# Schematic.net
KiCad netlist of a schematic drawn in Altium Designer
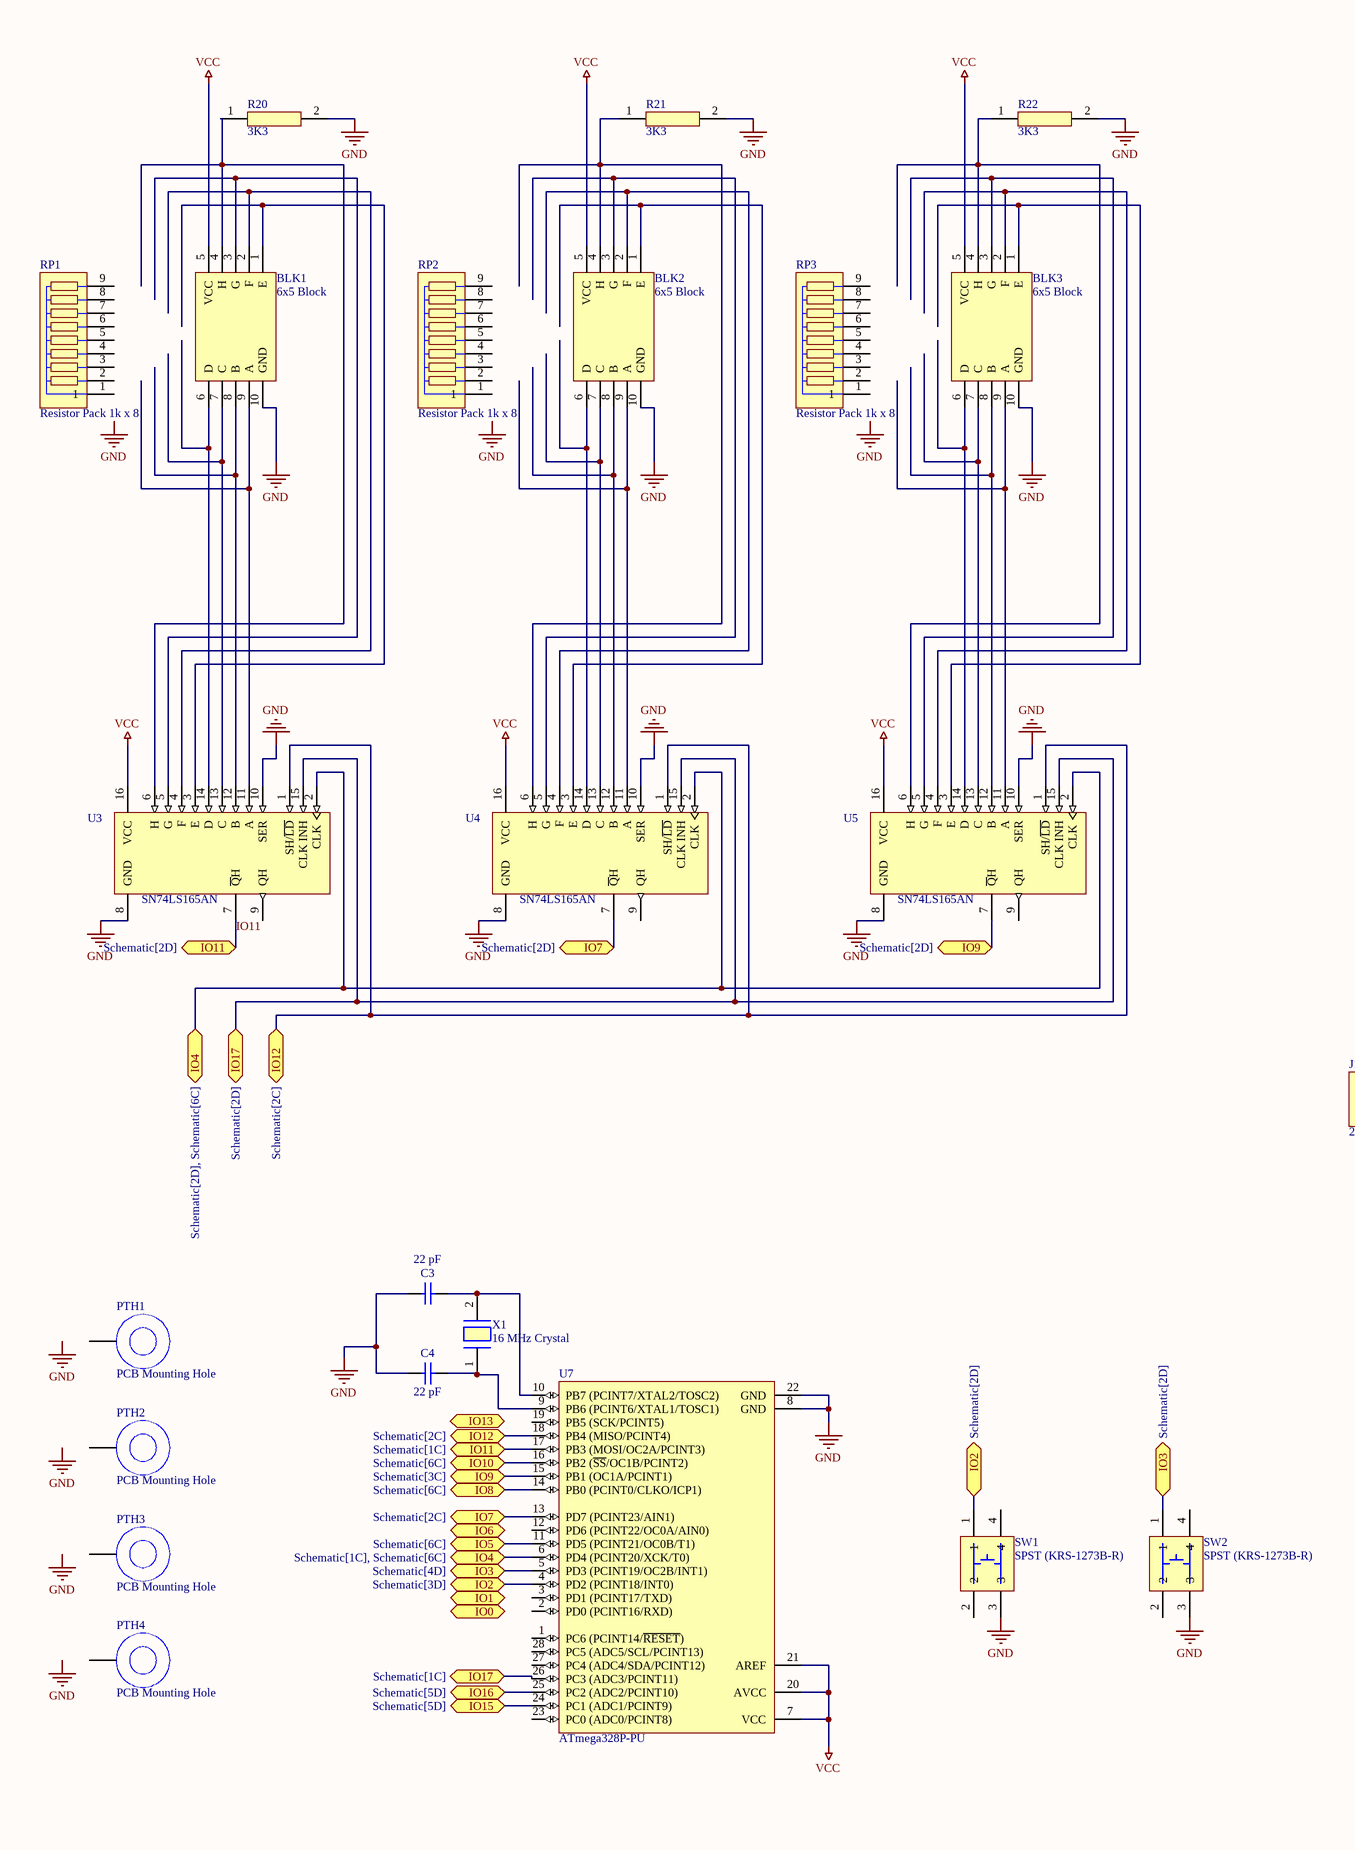
[diagram p0: Schematic.SchDoc, left]
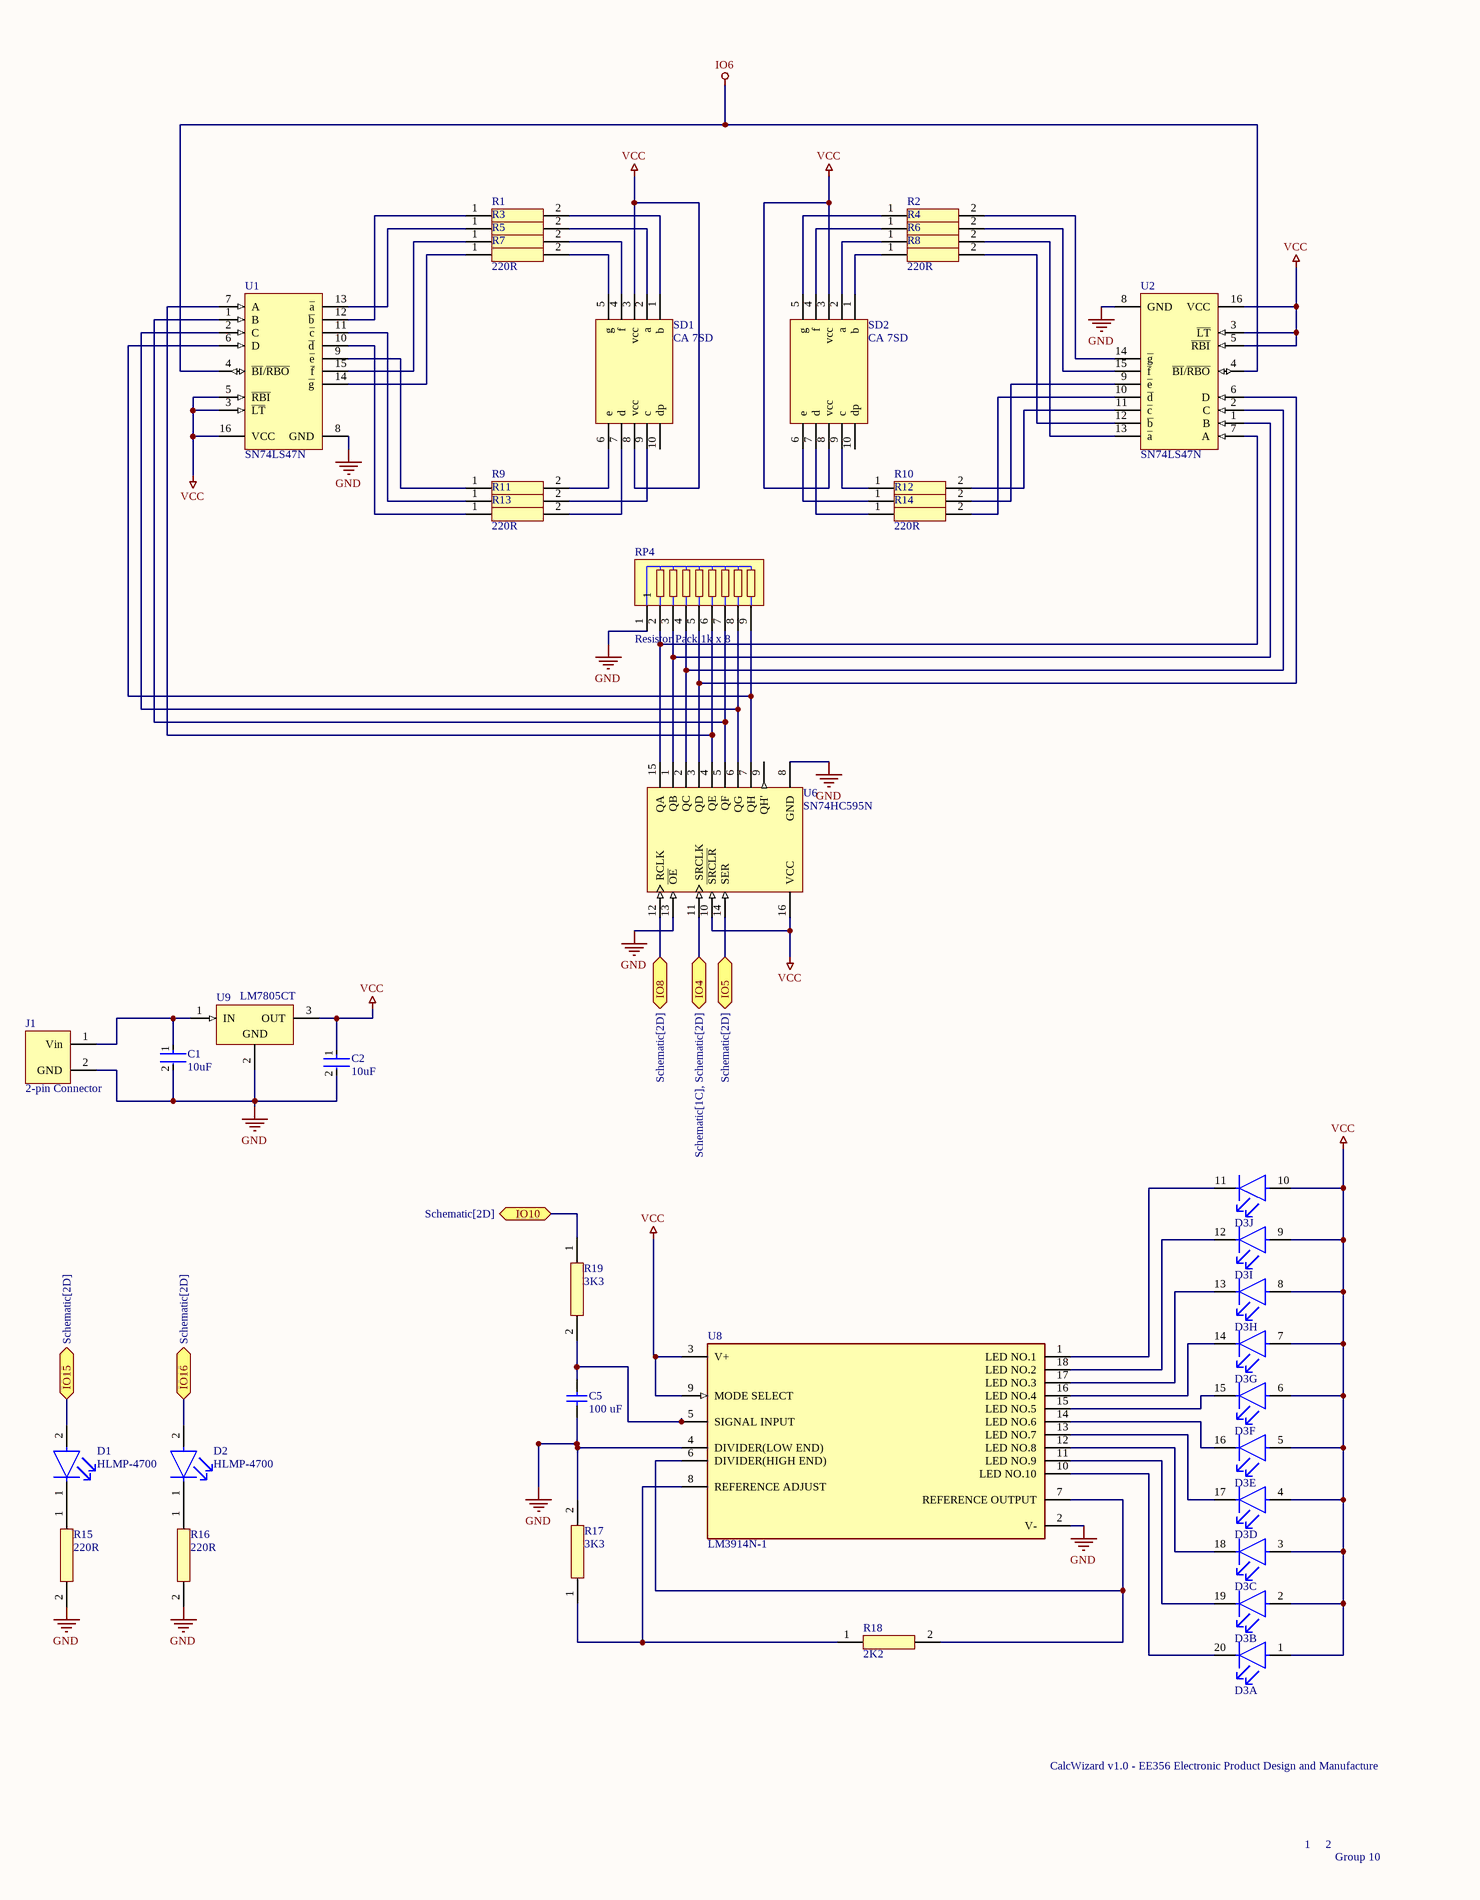
[diagram p1: Schematic.SchDoc, right]

(export (version "E")
  (design (tool "Eeschema 10.0.6"))
  (components
    (comp (ref "BLK1")
      (value "6x5 Block")
      (footprint "Block_6x5")
      (libsource (lib "Schlib1") (part "Block_6x5"))
    )
    (comp (ref "BLK2")
      (value "6x5 Block")
      (footprint "Block_6x5")
      (libsource (lib "Schlib1") (part "Block_6x5"))
    )
    (comp (ref "BLK3")
      (value "6x5 Block")
      (footprint "Block_6x5")
      (libsource (lib "Schlib1") (part "Block_6x5"))
    )
    (comp (ref "C1")
      (value "10uF")
      (footprint "FP-RCE3DB-MFG")
      (description "Cap Ceramic 10uF 25V X7R ±10% Radial 2.5mm +125°C Automotive Bulk (RCER71E106K3A2H03B)")
      (fields (field (name "TOLERANCE") "10%"))
      (libsource (lib "Altium Content Vault") (part "b4654b650e69147ec39a6b967a45e02"))
    )
    (comp (ref "C2")
      (value "10uF")
      (footprint "FP-RCE3DB-MFG")
      (description "Cap Ceramic 10uF 25V X7R ±10% Radial 2.5mm +125°C Automotive Bulk (RCER71E106K3A2H03B)")
      (fields (field (name "TOLERANCE") "10%"))
      (libsource (lib "Altium Content Vault") (part "b4654b650e69147ec39a6b967a45e02"))
    )
    (comp (ref "C3")
      (value "22 pF")
      (footprint "KEMT-C315-THT-2")
      (description "Capacitor, Ceramic, 22 pF, +/-10 %, 100 V, -55 to 125 degC, 2-Pin THD, RoHS, Bulk")
      (libsource (lib "Altium Content Vault") (part "CAP-NP-2"))
    )
    (comp (ref "C4")
      (value "22 pF")
      (footprint "KEMT-C315-THT-2")
      (description "Capacitor, Ceramic, 22 pF, +/-10 %, 100 V, -55 to 125 degC, 2-Pin THD, RoHS, Bulk")
      (libsource (lib "Altium Content Vault") (part "CAP-NP-2"))
    )
    (comp (ref "C5")
      (value "100 uF")
      (footprint "KEMT-C315-THT-2")
      (description "Capacitor, Ceramic, 100 uF, +/-10 %, 100 V, -55 to 125 degC, 2-Pin THD, RoHS, Bulk")
      (libsource (lib "Altium Content Vault") (part "CAP-NP-2"))
    )
    (comp (ref "D1")
      (value "HLMP-4700")
      (footprint "FP-HLMP-4700-MFG")
      (description "LED RED DIFFUSED T-1 3/4 T/H")
      (fields
        (field (name "OCTOPART") "https://octopart.com/hlmp-4700-broadcom-71130526")
        (field (name "MANUFACTURER") "Broadcom")
      )
      (libsource (lib "Altium Content Vault") (part "8706943c75ba83719d021d2fdc84c58"))
    )
    (comp (ref "D2")
      (value "HLMP-4700")
      (footprint "FP-HLMP-4700-MFG")
      (description "LED RED DIFFUSED T-1 3/4 T/H")
      (fields
        (field (name "OCTOPART") "https://octopart.com/hlmp-4700-broadcom-71130526")
        (field (name "MANUFACTURER") "Broadcom")
      )
      (libsource (lib "Altium Content Vault") (part "8706943c75ba83719d021d2fdc84c58"))
    )
    (comp (ref "D3")
      (value "SSA-LXB10HW-GF/LP")
      (footprint "FP-SSA-LXB10HW-GF-LP-MFG")
      (description "LED ARRAY 10X25MM 10SEG RED DIFF")
      (fields
        (field (name "OCTOPART") "https://octopart.com/ssa-lxb10hw-gf%2Flp-lumex-548235")
        (field (name "MANUFACTURER") "lumex")
      )
      (libsource (lib "Altium Content Vault") (part "0ad3f8813297581e4dba16f0763b6c7"))
    )
    (comp (ref "J1")
      (value "2-pin Connector")
      (footprint "2-pin Connector")
      (description "Female, 2C, Straight, .100\"CC; 3.20mm Tail, No Mt. 100u\" Tin; PBT, Phos Bronze, 105 C")
      (fields
        (field (name "MANUFACTURER") "Sullins")
        (field (name "MANUFACTURER PART NUMBER") "PPTC021LFBN-RC")
      )
      (libsource (lib "Schlib1") (part "PPTC021LFBN-RC"))
    )
    (comp (ref "PTH1")
      (value "PCB Mounting Hole")
      (footprint "PTH 2mm")
      (libsource (lib "Schlib1") (part "PTH"))
    )
    (comp (ref "PTH2")
      (value "PCB Mounting Hole")
      (footprint "PTH 2mm")
      (libsource (lib "Schlib1") (part "PTH"))
    )
    (comp (ref "PTH3")
      (value "PCB Mounting Hole")
      (footprint "PTH 2mm")
      (libsource (lib "Schlib1") (part "PTH"))
    )
    (comp (ref "PTH4")
      (value "PCB Mounting Hole")
      (footprint "PTH 2mm")
      (libsource (lib "Schlib1") (part "PTH"))
    )
    (comp (ref "R1")
      (value "220R")
      (footprint "CFR_400mil")
      (description "General Type Carbon Film Resistor 220Ohm 1/4W 5% Axial Bulk")
      (fields
        (field (name "MANUFACTURER") "Yageo")
        (field (name "MANUFACTURER PART NUMBER") "CFR-25JB-52-220R")
      )
      (libsource (lib "Schlib1") (part "CFR-25JB-52-220R"))
    )
    (comp (ref "R2")
      (value "220R")
      (footprint "CFR_400mil")
      (description "General Type Carbon Film Resistor 220Ohm 1/4W 5% Axial Bulk")
      (fields
        (field (name "MANUFACTURER") "Yageo")
        (field (name "MANUFACTURER PART NUMBER") "CFR-25JB-52-220R")
      )
      (libsource (lib "Schlib1") (part "CFR-25JB-52-220R"))
    )
    (comp (ref "R3")
      (value "220R")
      (footprint "CFR_400mil")
      (description "General Type Carbon Film Resistor 220Ohm 1/4W 5% Axial Bulk")
      (fields
        (field (name "MANUFACTURER") "Yageo")
        (field (name "MANUFACTURER PART NUMBER") "CFR-25JB-52-220R")
      )
      (libsource (lib "Schlib1") (part "CFR-25JB-52-220R"))
    )
    (comp (ref "R4")
      (value "220R")
      (footprint "CFR_400mil")
      (description "General Type Carbon Film Resistor 220Ohm 1/4W 5% Axial Bulk")
      (fields
        (field (name "MANUFACTURER") "Yageo")
        (field (name "MANUFACTURER PART NUMBER") "CFR-25JB-52-220R")
      )
      (libsource (lib "Schlib1") (part "CFR-25JB-52-220R"))
    )
    (comp (ref "R5")
      (value "220R")
      (footprint "CFR_400mil")
      (description "General Type Carbon Film Resistor 220Ohm 1/4W 5% Axial Bulk")
      (fields
        (field (name "MANUFACTURER") "Yageo")
        (field (name "MANUFACTURER PART NUMBER") "CFR-25JB-52-220R")
      )
      (libsource (lib "Schlib1") (part "CFR-25JB-52-220R"))
    )
    (comp (ref "R6")
      (value "220R")
      (footprint "CFR_400mil")
      (description "General Type Carbon Film Resistor 220Ohm 1/4W 5% Axial Bulk")
      (fields
        (field (name "MANUFACTURER") "Yageo")
        (field (name "MANUFACTURER PART NUMBER") "CFR-25JB-52-220R")
      )
      (libsource (lib "Schlib1") (part "CFR-25JB-52-220R"))
    )
    (comp (ref "R7")
      (value "220R")
      (footprint "CFR_400mil")
      (description "General Type Carbon Film Resistor 220Ohm 1/4W 5% Axial Bulk")
      (fields
        (field (name "MANUFACTURER") "Yageo")
        (field (name "MANUFACTURER PART NUMBER") "CFR-25JB-52-220R")
      )
      (libsource (lib "Schlib1") (part "CFR-25JB-52-220R"))
    )
    (comp (ref "R8")
      (value "220R")
      (footprint "CFR_400mil")
      (description "General Type Carbon Film Resistor 220Ohm 1/4W 5% Axial Bulk")
      (fields
        (field (name "MANUFACTURER") "Yageo")
        (field (name "MANUFACTURER PART NUMBER") "CFR-25JB-52-220R")
      )
      (libsource (lib "Schlib1") (part "CFR-25JB-52-220R"))
    )
    (comp (ref "R9")
      (value "220R")
      (footprint "CFR_400mil")
      (description "General Type Carbon Film Resistor 220Ohm 1/4W 5% Axial Bulk")
      (fields
        (field (name "MANUFACTURER") "Yageo")
        (field (name "MANUFACTURER PART NUMBER") "CFR-25JB-52-220R")
      )
      (libsource (lib "Schlib1") (part "CFR-25JB-52-220R"))
    )
    (comp (ref "R10")
      (value "220R")
      (footprint "CFR_400mil")
      (description "General Type Carbon Film Resistor 220Ohm 1/4W 5% Axial Bulk")
      (fields
        (field (name "MANUFACTURER") "Yageo")
        (field (name "MANUFACTURER PART NUMBER") "CFR-25JB-52-220R")
      )
      (libsource (lib "Schlib1") (part "CFR-25JB-52-220R"))
    )
    (comp (ref "R11")
      (value "220R")
      (footprint "CFR_400mil")
      (description "General Type Carbon Film Resistor 220Ohm 1/4W 5% Axial Bulk")
      (fields
        (field (name "MANUFACTURER") "Yageo")
        (field (name "MANUFACTURER PART NUMBER") "CFR-25JB-52-220R")
      )
      (libsource (lib "Schlib1") (part "CFR-25JB-52-220R"))
    )
    (comp (ref "R12")
      (value "220R")
      (footprint "CFR_400mil")
      (description "General Type Carbon Film Resistor 220Ohm 1/4W 5% Axial Bulk")
      (fields
        (field (name "MANUFACTURER") "Yageo")
        (field (name "MANUFACTURER PART NUMBER") "CFR-25JB-52-220R")
      )
      (libsource (lib "Schlib1") (part "CFR-25JB-52-220R"))
    )
    (comp (ref "R13")
      (value "220R")
      (footprint "CFR_400mil")
      (description "General Type Carbon Film Resistor 220Ohm 1/4W 5% Axial Bulk")
      (fields
        (field (name "MANUFACTURER") "Yageo")
        (field (name "MANUFACTURER PART NUMBER") "CFR-25JB-52-220R")
      )
      (libsource (lib "Schlib1") (part "CFR-25JB-52-220R"))
    )
    (comp (ref "R14")
      (value "220R")
      (footprint "CFR_400mil")
      (description "General Type Carbon Film Resistor 220Ohm 1/4W 5% Axial Bulk")
      (fields
        (field (name "MANUFACTURER") "Yageo")
        (field (name "MANUFACTURER PART NUMBER") "CFR-25JB-52-220R")
      )
      (libsource (lib "Schlib1") (part "CFR-25JB-52-220R"))
    )
    (comp (ref "R15")
      (value "220R")
      (footprint "CFR_400mil")
      (description "General Type Carbon Film Resistor 220Ohm 1/4W 5% Axial Bulk")
      (fields
        (field (name "MANUFACTURER") "Yageo")
        (field (name "MANUFACTURER PART NUMBER") "CFR-25JB-52-220R")
      )
      (libsource (lib "") (part "CFR-25JB-52-220R_1"))
    )
    (comp (ref "R16")
      (value "220R")
      (footprint "CFR_400mil")
      (description "General Type Carbon Film Resistor 220Ohm 1/4W 5% Axial Bulk")
      (fields
        (field (name "MANUFACTURER") "Yageo")
        (field (name "MANUFACTURER PART NUMBER") "CFR-25JB-52-220R")
      )
      (libsource (lib "") (part "CFR-25JB-52-220R_1"))
    )
    (comp (ref "R17")
      (value "3K3")
      (footprint "CFR_400mil")
      (description "General Type Carbon Film Resistor 3.3kOhm 1/4W 5% Axial Bulk")
      (fields
        (field (name "MANUFACTURER") "Yageo")
        (field (name "MANUFACTURER PART NUMBER") "CFR-25JB-52-220R")
      )
      (libsource (lib "Schlib1") (part "CFR-25JB-52-3K3"))
    )
    (comp (ref "R18")
      (value "2K2")
      (footprint "CFR_400mil")
      (description "General Type Carbon Film Resistor 2.2kOhm 1/4W 5% Axial Bulk")
      (fields
        (field (name "MANUFACTURER") "Yageo")
        (field (name "MANUFACTURER PART NUMBER") "CFR-25JB-52-220R")
      )
      (libsource (lib "Schlib1") (part "CFR-25JB-52-2K2"))
    )
    (comp (ref "R19")
      (value "3K3")
      (footprint "CFR_400mil")
      (description "General Type Carbon Film Resistor 3.3kOhm 1/4W 5% Axial Bulk")
      (fields
        (field (name "MANUFACTURER") "Yageo")
        (field (name "MANUFACTURER PART NUMBER") "CFR-25JB-52-220R")
      )
      (libsource (lib "") (part "CFR-25JB-52-3K3_2"))
    )
    (comp (ref "R20")
      (value "3K3")
      (footprint "CFR_400mil")
      (description "General Type Carbon Film Resistor 3.3kOhm 1/4W 5% Axial Bulk")
      (fields
        (field (name "MANUFACTURER") "Yageo")
        (field (name "MANUFACTURER PART NUMBER") "CFR-25JB-52-220R")
      )
      (libsource (lib "") (part "CFR-25JB-52-3K3_1"))
    )
    (comp (ref "R21")
      (value "3K3")
      (footprint "CFR_400mil")
      (description "General Type Carbon Film Resistor 3.3kOhm 1/4W 5% Axial Bulk")
      (fields
        (field (name "MANUFACTURER") "Yageo")
        (field (name "MANUFACTURER PART NUMBER") "CFR-25JB-52-220R")
      )
      (libsource (lib "") (part "CFR-25JB-52-3K3_1"))
    )
    (comp (ref "R22")
      (value "3K3")
      (footprint "CFR_400mil")
      (description "General Type Carbon Film Resistor 3.3kOhm 1/4W 5% Axial Bulk")
      (fields
        (field (name "MANUFACTURER") "Yageo")
        (field (name "MANUFACTURER PART NUMBER") "CFR-25JB-52-220R")
      )
      (libsource (lib "") (part "CFR-25JB-52-3K3_1"))
    )
    (comp (ref "RP1")
      (value "Resistor Pack 1k x 8")
      (footprint "Resistor Pack 1k x 8")
      (description "Res Thick Film NET 1K Ohm 2% 1.13W ±100ppm/°C BUS Molded 9-Pin SIP Pin Thru-Hole")
      (fields
        (field (name "MANUFACTURER") "Bourns")
        (field (name "MANUFACTURER PART NUMBER") "4309R-101-102LF")
      )
      (libsource (lib "") (part "4309R-101-102LF_1"))
    )
    (comp (ref "RP2")
      (value "Resistor Pack 1k x 8")
      (footprint "Resistor Pack 1k x 8")
      (description "Res Thick Film NET 1K Ohm 2% 1.13W ±100ppm/°C BUS Molded 9-Pin SIP Pin Thru-Hole")
      (fields
        (field (name "MANUFACTURER") "Bourns")
        (field (name "MANUFACTURER PART NUMBER") "4309R-101-102LF")
      )
      (libsource (lib "") (part "4309R-101-102LF_1"))
    )
    (comp (ref "RP3")
      (value "Resistor Pack 1k x 8")
      (footprint "Resistor Pack 1k x 8")
      (description "Res Thick Film NET 1K Ohm 2% 1.13W ±100ppm/°C BUS Molded 9-Pin SIP Pin Thru-Hole")
      (fields
        (field (name "MANUFACTURER") "Bourns")
        (field (name "MANUFACTURER PART NUMBER") "4309R-101-102LF")
      )
      (libsource (lib "") (part "4309R-101-102LF_1"))
    )
    (comp (ref "RP4")
      (value "Resistor Pack 1k x 8")
      (footprint "Resistor Pack 1k x 8")
      (description "Res Thick Film NET 1K Ohm 2% 1.13W ±100ppm/°C BUS Molded 9-Pin SIP Pin Thru-Hole")
      (fields
        (field (name "MANUFACTURER") "Bourns")
        (field (name "MANUFACTURER PART NUMBER") "4309R-101-102LF")
      )
      (libsource (lib "Schlib1") (part "4309R-101-102LF"))
    )
    (comp (ref "SD1")
      (value "CA 7SD")
      (footprint "CA 7SD")
      (description "Single Digit Seven Segment Green 0.56\" Common Anode Through Hole LED Display")
      (fields (field (name "MANUFACTURER") "Lumex") (field (name "MANUFACTURER PART NUMBER") "LDS-A5642RI"))
      (libsource (lib "Schlib1") (part "LDS-A5642RI"))
    )
    (comp (ref "SD2")
      (value "CA 7SD")
      (footprint "CA 7SD")
      (description "Single Digit Seven Segment Green 0.56\" Common Anode Through Hole LED Display")
      (fields (field (name "MANUFACTURER") "Lumex") (field (name "MANUFACTURER PART NUMBER") "LDS-A5642RI"))
      (libsource (lib "Schlib1") (part "LDS-A5642RI"))
    )
    (comp (ref "SW1")
      (value "SPST (KRS-1273B-R)")
      (footprint "SPST KRS-1273B-R")
      (description "Switch Push Button Tactile Off Momentary (On) Single Pole Single Throw Cap: 155389 155409")
      (fields
        (field (name "MANUFACTURER") "Jameco Valuepro")
        (field (name "MANUFACTURER PART NUMBER") "KRS-1273B-R")
      )
      (libsource (lib "Schlib1") (part "KRS-1273B-R"))
    )
    (comp (ref "SW2")
      (value "SPST (KRS-1273B-R)")
      (footprint "SPST KRS-1273B-R")
      (description "Switch Push Button Tactile Off Momentary (On) Single Pole Single Throw Cap: 155389 155409")
      (fields
        (field (name "MANUFACTURER") "Jameco Valuepro")
        (field (name "MANUFACTURER PART NUMBER") "KRS-1273B-R")
      )
      (libsource (lib "Schlib1") (part "KRS-1273B-R"))
    )
    (comp (ref "U1")
      (value "SN74LS47N")
      (footprint "N0016A")
      (description "BCD-to-7-Segment Decoder / Driver, 4.75 to 5.25 V, 0 to 70 degC, 16-pin DIP (N16), Pb-Free (RoHS)")
      (fields (field (name "MANUFACTURER") "Texas Instruments"))
      (libsource (lib "") (part "TI-SNX4XX247-16_1"))
    )
    (comp (ref "U2")
      (value "SN74LS47N")
      (footprint "N0016A")
      (description "BCD-to-7-Segment Decoder / Driver, 4.75 to 5.25 V, 0 to 70 degC, 16-pin DIP (N16), Pb-Free (RoHS)")
      (fields (field (name "MANUFACTURER") "Texas Instruments"))
      (libsource (lib "Altium Content Vault") (part "TI-SNX4XX247-16"))
    )
    (comp (ref "U3")
      (value "SN74LS165AN")
      (footprint "N0016A")
      (description "Serial-out shift registers, N0016A, TUBE")
      (fields
        (field (name "GENERIC PART NUMBER") "SN74LS165A")
        (field (name "MANUFACTURER") "Texas Instruments")
      )
      (libsource (lib "Altium Content Vault") (part "TI-SNX4XXX165X-16"))
    )
    (comp (ref "U4")
      (value "SN74LS165AN")
      (footprint "N0016A")
      (description "Serial-out shift registers, N0016A, TUBE")
      (fields
        (field (name "GENERIC PART NUMBER") "SN74LS165A")
        (field (name "MANUFACTURER") "Texas Instruments")
      )
      (libsource (lib "Altium Content Vault") (part "TI-SNX4XXX165X-16"))
    )
    (comp (ref "U5")
      (value "SN74LS165AN")
      (footprint "N0016A")
      (description "Serial-out shift registers, N0016A, TUBE")
      (fields
        (field (name "GENERIC PART NUMBER") "SN74LS165A")
        (field (name "MANUFACTURER") "Texas Instruments")
      )
      (libsource (lib "Altium Content Vault") (part "TI-SNX4XXX165X-16"))
    )
    (comp (ref "U6")
      (value "SN74HC595N")
      (footprint "N0016A")
      (description "8-Bit Shift Registers With 3-State Output Registers, N0016A, TUBE")
      (fields
        (field (name "GENERIC PART NUMBER") "SN74HC595")
        (field (name "MANUFACTURER") "Texas Instruments")
      )
      (libsource (lib "Altium Content Vault") (part "TI-SN74XHCT595X_SN74LV595A-16"))
    )
    (comp (ref "U7")
      (value "ATmega328P-PU")
      (footprint "28P3")
      (libsource (lib "Altium Content Vault") (part "MC-8B-ATM48-IL28"))
    )
    (comp (ref "U8")
      (value "LM3914N-1")
      (footprint "FP-NFK0018A-MFG")
      (description "IC DRVR DOT/BAR DISPLAY 18DIP")
      (libsource (lib "Altium Content Vault") (part "8d9105b9cf50def005be23956edfdd2"))
    )
    (comp (ref "U9")
      (value "LM7805CT")
      (footprint "FAIR-TO-220-3")
      (description "Positive Voltage Regulator, 5 V, 1 A, -40 to 125 degC, 3-Pin TO-220, RoHS, Tube")
      (fields (field (name "MANUFACTURER") "FairchildSemiconductor"))
      (libsource (lib "Altium Content Vault") (part "FAIR-LM7805CT-TO220-3"))
    )
    (comp (ref "X1")
      (value "16 MHz Crystal")
      (footprint "Crystal Osc TH")
      (description "Crystal 16MHz ±50ppm (Tol) ±50ppm (Stability) 20pF FUND 30Ohm 2-Pin DIP HC-49/S Thru-Hole Bulk")
      (fields (field (name "MANUFACTURER") "TXC") (field (name "MANUFACTURER PART NUMBER") "9B-16.000MBBK-B"))
      (libsource (lib "Schlib1") (part "9B-16.000MBBK-B"))
    )
  )
  (nets
    (net (code "3") (name "/IO2") (class "Default")
      (node (ref "SW1") (pin "1") (pinfunction "1_1") (pintype "passive"))
      (node (ref "U7") (pin "4") (pinfunction "PD2_(PCINT18/INT0)_4") (pintype "bidirectional"))
    )
    (net (code "4") (name "/IO3") (class "Default")
      (node (ref "SW2") (pin "1") (pinfunction "1_1") (pintype "passive"))
      (node (ref "U7") (pin "5") (pinfunction "PD3_(PCINT19/OC2B/INT1)_5") (pintype "bidirectional"))
    )
    (net (code "5") (name "/IO4") (class "Default")
      (node (ref "U3") (pin "2") (pinfunction "CLK_2") (pintype "input"))
      (node (ref "U4") (pin "2") (pinfunction "CLK_2") (pintype "input"))
      (node (ref "U5") (pin "2") (pinfunction "CLK_2") (pintype "input"))
      (node (ref "U6") (pin "11") (pinfunction "SRCLK_11") (pintype "input"))
      (node (ref "U7") (pin "6") (pinfunction "PD4_(PCINT20/XCK/T0)_6") (pintype "bidirectional"))
    )
    (net (code "6") (name "/IO5") (class "Default")
      (node (ref "U6") (pin "14") (pinfunction "SER_14") (pintype "input"))
      (node (ref "U7") (pin "11") (pinfunction "PD5_(PCINT21/OC0B/T1)_11") (pintype "bidirectional"))
    )
    (net (code "7") (name "/IO7") (class "Default")
      (node (ref "U4") (pin "7") (pinfunction "~{Q}H_7") (pintype "passive"))
      (node (ref "U7") (pin "13") (pinfunction "PD7_(PCINT23/AIN1)_13") (pintype "bidirectional"))
    )
    (net (code "8") (name "/IO8") (class "Default")
      (node (ref "U6") (pin "12") (pinfunction "RCLK_12") (pintype "input"))
      (node (ref "U7") (pin "14") (pinfunction "PB0_(PCINT0/CLKO/ICP1)_14") (pintype "bidirectional"))
    )
    (net (code "9") (name "/IO9") (class "Default")
      (node (ref "U5") (pin "7") (pinfunction "~{Q}H_7") (pintype "passive"))
      (node (ref "U7") (pin "15") (pinfunction "PB1_(OC1A/PCINT1)_15") (pintype "bidirectional"))
    )
    (net (code "10") (name "/IO10") (class "Default")
      (node (ref "R19") (pin "1") (pinfunction "1_1") (pintype "passive"))
      (node (ref "U7") (pin "16") (pinfunction "PB2_(~{SS}/OC1B/PCINT2)_16") (pintype "bidirectional"))
    )
    (net (code "11") (name "/IO11") (class "Default")
      (node (ref "U3") (pin "7") (pinfunction "~{Q}H_7") (pintype "passive"))
      (node (ref "U7") (pin "17") (pinfunction "PB3_(MOSI/OC2A/PCINT3)_17") (pintype "bidirectional"))
    )
    (net (code "12") (name "/IO12") (class "Default")
      (node (ref "U3") (pin "1") (pinfunction "SH/~{LD}_1") (pintype "input"))
      (node (ref "U4") (pin "1") (pinfunction "SH/~{LD}_1") (pintype "input"))
      (node (ref "U5") (pin "1") (pinfunction "SH/~{LD}_1") (pintype "input"))
      (node (ref "U7") (pin "18") (pinfunction "PB4_(MISO/PCINT4)_18") (pintype "bidirectional"))
    )
    (net (code "14") (name "/IO15") (class "Default")
      (node (ref "D1") (pin "2") (pinfunction "A_2") (pintype "passive"))
      (node (ref "U7") (pin "24") (pinfunction "PC1_(ADC1/PCINT9)_24") (pintype "bidirectional"))
    )
    (net (code "15") (name "/IO16") (class "Default")
      (node (ref "D2") (pin "2") (pinfunction "A_2") (pintype "passive"))
      (node (ref "U7") (pin "25") (pinfunction "PC2_(ADC2/PCINT10)_25") (pintype "bidirectional"))
    )
    (net (code "16") (name "/IO17") (class "Default")
      (node (ref "U3") (pin "15") (pinfunction "CLK_INH_15") (pintype "input"))
      (node (ref "U4") (pin "15") (pinfunction "CLK_INH_15") (pintype "input"))
      (node (ref "U5") (pin "15") (pinfunction "CLK_INH_15") (pintype "input"))
      (node (ref "U7") (pin "26") (pinfunction "PC3_(ADC3/PCINT11)_26") (pintype "bidirectional"))
    )
    (net (code "17") (name "GND") (class "Default")
      (node (ref "BLK1") (pin "10") (pinfunction "GND_10") (pintype "passive"))
      (node (ref "BLK2") (pin "10") (pinfunction "GND_10") (pintype "passive"))
      (node (ref "BLK3") (pin "10") (pinfunction "GND_10") (pintype "passive"))
      (node (ref "C1") (pin "2") (pinfunction "2_2") (pintype "passive"))
      (node (ref "C2") (pin "2") (pinfunction "2_2") (pintype "passive"))
      (node (ref "C3") (pin "1") (pinfunction "1_1") (pintype "passive"))
      (node (ref "C4") (pin "1") (pinfunction "1_1") (pintype "passive"))
      (node (ref "C5") (pin "1") (pinfunction "1_1") (pintype "passive"))
      (node (ref "J1") (pin "2") (pinfunction "GND_2") (pintype "passive"))
      (node (ref "R15") (pin "2") (pinfunction "2_2") (pintype "passive"))
      (node (ref "R16") (pin "2") (pinfunction "2_2") (pintype "passive"))
      (node (ref "R17") (pin "2") (pinfunction "2_2") (pintype "passive"))
      (node (ref "R20") (pin "2") (pinfunction "2_2") (pintype "passive"))
      (node (ref "R21") (pin "2") (pinfunction "2_2") (pintype "passive"))
      (node (ref "R22") (pin "2") (pinfunction "2_2") (pintype "passive"))
      (node (ref "RP4") (pin "1") (pinfunction "1_1") (pintype "passive"))
      (node (ref "SW1") (pin "3") (pinfunction "3_3") (pintype "passive"))
      (node (ref "SW2") (pin "3") (pinfunction "3_3") (pintype "passive"))
      (node (ref "U1") (pin "8") (pinfunction "GND_8") (pintype "power_in"))
      (node (ref "U2") (pin "8") (pinfunction "GND_8") (pintype "power_in"))
      (node (ref "U3") (pin "10") (pinfunction "SER_10") (pintype "input"))
      (node (ref "U3") (pin "8") (pinfunction "GND_8") (pintype "power_in"))
      (node (ref "U4") (pin "10") (pinfunction "SER_10") (pintype "input"))
      (node (ref "U4") (pin "8") (pinfunction "GND_8") (pintype "power_in"))
      (node (ref "U5") (pin "10") (pinfunction "SER_10") (pintype "input"))
      (node (ref "U5") (pin "8") (pinfunction "GND_8") (pintype "power_in"))
      (node (ref "U6") (pin "13") (pinfunction "~{OE}_13") (pintype "input"))
      (node (ref "U6") (pin "8") (pinfunction "GND_8") (pintype "power_in"))
      (node (ref "U7") (pin "22") (pinfunction "GND_22") (pintype "power_in"))
      (node (ref "U7") (pin "8") (pinfunction "GND_8") (pintype "power_in"))
      (node (ref "U8") (pin "2") (pinfunction "V-_2") (pintype "power_in"))
      (node (ref "U8") (pin "4") (pinfunction "DIVIDER(LOW_END)_4") (pintype "passive"))
      (node (ref "U9") (pin "2") (pinfunction "GND_2") (pintype "power_in"))
    )
    (net (code "18") (name "IO6") (class "Default")
      (node (ref "U1") (pin "4") (pinfunction "~{BI}/~{RBO}_4") (pintype "bidirectional"))
      (node (ref "U2") (pin "4") (pinfunction "~{BI}/~{RBO}_4") (pintype "bidirectional"))
    )
    (net (code "19") (name "Net-(BLK1-A)") (class "Default")
      (node (ref "BLK1") (pin "9") (pinfunction "A_9") (pintype "passive"))
      (node (ref "U3") (pin "11") (pinfunction "A_11") (pintype "input"))
    )
    (net (code "20") (name "Net-(BLK1-B)") (class "Default")
      (node (ref "BLK1") (pin "8") (pinfunction "B_8") (pintype "passive"))
      (node (ref "U3") (pin "12") (pinfunction "B_12") (pintype "input"))
    )
    (net (code "21") (name "Net-(BLK1-C)") (class "Default")
      (node (ref "BLK1") (pin "7") (pinfunction "C_7") (pintype "passive"))
      (node (ref "U3") (pin "13") (pinfunction "C_13") (pintype "input"))
    )
    (net (code "22") (name "Net-(BLK1-D)") (class "Default")
      (node (ref "BLK1") (pin "6") (pinfunction "D_6") (pintype "passive"))
      (node (ref "U3") (pin "14") (pinfunction "D_14") (pintype "input"))
    )
    (net (code "23") (name "Net-(BLK1-E)") (class "Default")
      (node (ref "BLK1") (pin "1") (pinfunction "E_1") (pintype "passive"))
      (node (ref "U3") (pin "3") (pinfunction "E_3") (pintype "input"))
    )
    (net (code "24") (name "Net-(BLK1-F)") (class "Default")
      (node (ref "BLK1") (pin "2") (pinfunction "F_2") (pintype "passive"))
      (node (ref "U3") (pin "4") (pinfunction "F_4") (pintype "input"))
    )
    (net (code "25") (name "Net-(BLK1-G)") (class "Default")
      (node (ref "BLK1") (pin "3") (pinfunction "G_3") (pintype "passive"))
      (node (ref "U3") (pin "5") (pinfunction "G_5") (pintype "input"))
    )
    (net (code "26") (name "Net-(BLK1-H)") (class "Default")
      (node (ref "BLK1") (pin "4") (pinfunction "H_4") (pintype "passive"))
      (node (ref "R20") (pin "1") (pinfunction "1_1") (pintype "passive"))
      (node (ref "U3") (pin "6") (pinfunction "H_6") (pintype "input"))
    )
    (net (code "27") (name "Net-(BLK2-A)") (class "Default")
      (node (ref "BLK2") (pin "9") (pinfunction "A_9") (pintype "passive"))
      (node (ref "U4") (pin "11") (pinfunction "A_11") (pintype "input"))
    )
    (net (code "28") (name "Net-(BLK2-B)") (class "Default")
      (node (ref "BLK2") (pin "8") (pinfunction "B_8") (pintype "passive"))
      (node (ref "U4") (pin "12") (pinfunction "B_12") (pintype "input"))
    )
    (net (code "29") (name "Net-(BLK2-C)") (class "Default")
      (node (ref "BLK2") (pin "7") (pinfunction "C_7") (pintype "passive"))
      (node (ref "U4") (pin "13") (pinfunction "C_13") (pintype "input"))
    )
    (net (code "30") (name "Net-(BLK2-D)") (class "Default")
      (node (ref "BLK2") (pin "6") (pinfunction "D_6") (pintype "passive"))
      (node (ref "U4") (pin "14") (pinfunction "D_14") (pintype "input"))
    )
    (net (code "31") (name "Net-(BLK2-E)") (class "Default")
      (node (ref "BLK2") (pin "1") (pinfunction "E_1") (pintype "passive"))
      (node (ref "U4") (pin "3") (pinfunction "E_3") (pintype "input"))
    )
    (net (code "32") (name "Net-(BLK2-F)") (class "Default")
      (node (ref "BLK2") (pin "2") (pinfunction "F_2") (pintype "passive"))
      (node (ref "U4") (pin "4") (pinfunction "F_4") (pintype "input"))
    )
    (net (code "33") (name "Net-(BLK2-G)") (class "Default")
      (node (ref "BLK2") (pin "3") (pinfunction "G_3") (pintype "passive"))
      (node (ref "U4") (pin "5") (pinfunction "G_5") (pintype "input"))
    )
    (net (code "34") (name "Net-(BLK2-H)") (class "Default")
      (node (ref "BLK2") (pin "4") (pinfunction "H_4") (pintype "passive"))
      (node (ref "R21") (pin "1") (pinfunction "1_1") (pintype "passive"))
      (node (ref "U4") (pin "6") (pinfunction "H_6") (pintype "input"))
    )
    (net (code "35") (name "Net-(BLK3-A)") (class "Default")
      (node (ref "BLK3") (pin "9") (pinfunction "A_9") (pintype "passive"))
      (node (ref "U5") (pin "11") (pinfunction "A_11") (pintype "input"))
    )
    (net (code "36") (name "Net-(BLK3-B)") (class "Default")
      (node (ref "BLK3") (pin "8") (pinfunction "B_8") (pintype "passive"))
      (node (ref "U5") (pin "12") (pinfunction "B_12") (pintype "input"))
    )
    (net (code "37") (name "Net-(BLK3-C)") (class "Default")
      (node (ref "BLK3") (pin "7") (pinfunction "C_7") (pintype "passive"))
      (node (ref "U5") (pin "13") (pinfunction "C_13") (pintype "input"))
    )
    (net (code "38") (name "Net-(BLK3-D)") (class "Default")
      (node (ref "BLK3") (pin "6") (pinfunction "D_6") (pintype "passive"))
      (node (ref "U5") (pin "14") (pinfunction "D_14") (pintype "input"))
    )
    (net (code "39") (name "Net-(BLK3-E)") (class "Default")
      (node (ref "BLK3") (pin "1") (pinfunction "E_1") (pintype "passive"))
      (node (ref "U5") (pin "3") (pinfunction "E_3") (pintype "input"))
    )
    (net (code "40") (name "Net-(BLK3-F)") (class "Default")
      (node (ref "BLK3") (pin "2") (pinfunction "F_2") (pintype "passive"))
      (node (ref "U5") (pin "4") (pinfunction "F_4") (pintype "input"))
    )
    (net (code "41") (name "Net-(BLK3-G)") (class "Default")
      (node (ref "BLK3") (pin "3") (pinfunction "G_3") (pintype "passive"))
      (node (ref "U5") (pin "5") (pinfunction "G_5") (pintype "input"))
    )
    (net (code "42") (name "Net-(BLK3-H)") (class "Default")
      (node (ref "BLK3") (pin "4") (pinfunction "H_4") (pintype "passive"))
      (node (ref "R22") (pin "1") (pinfunction "1_1") (pintype "passive"))
      (node (ref "U5") (pin "6") (pinfunction "H_6") (pintype "input"))
    )
    (net (code "43") (name "Net-(D1-C)") (class "Default")
      (node (ref "D1") (pin "1") (pinfunction "C_1") (pintype "passive"))
      (node (ref "R15") (pin "1") (pinfunction "1_1") (pintype "passive"))
    )
    (net (code "44") (name "Net-(D2-C)") (class "Default")
      (node (ref "D2") (pin "1") (pinfunction "C_1") (pintype "passive"))
      (node (ref "R16") (pin "1") (pinfunction "1_1") (pintype "passive"))
    )
    (net (code "45") (name "Net-(D3A-1_CATHODE)") (class "Default")
      (node (ref "D3") (pin "20") (pinfunction "1_CATHODE_20") (pintype "passive"))
      (node (ref "U8") (pin "10") (pinfunction "LED_NO.10_10") (pintype "passive"))
    )
    (net (code "46") (name "Net-(D3B-2_CATHODE)") (class "Default")
      (node (ref "D3") (pin "19") (pinfunction "2_CATHODE_19") (pintype "passive"))
      (node (ref "U8") (pin "11") (pinfunction "LED_NO.9_11") (pintype "passive"))
    )
    (net (code "47") (name "Net-(D3C-3_CATHODE)") (class "Default")
      (node (ref "D3") (pin "18") (pinfunction "3_CATHODE_18") (pintype "passive"))
      (node (ref "U8") (pin "12") (pinfunction "LED_NO.8_12") (pintype "passive"))
    )
    (net (code "48") (name "Net-(D3D-4_CATHODE)") (class "Default")
      (node (ref "D3") (pin "17") (pinfunction "4_CATHODE_17") (pintype "passive"))
      (node (ref "U8") (pin "13") (pinfunction "LED_NO.7_13") (pintype "passive"))
    )
    (net (code "49") (name "Net-(D3E-5_CATHODE)") (class "Default")
      (node (ref "D3") (pin "16") (pinfunction "5_CATHODE_16") (pintype "passive"))
      (node (ref "U8") (pin "14") (pinfunction "LED_NO.6_14") (pintype "passive"))
    )
    (net (code "50") (name "Net-(D3F-6_CATHODE)") (class "Default")
      (node (ref "D3") (pin "15") (pinfunction "6_CATHODE_15") (pintype "passive"))
      (node (ref "U8") (pin "15") (pinfunction "LED_NO.5_15") (pintype "passive"))
    )
    (net (code "51") (name "Net-(D3G-7_CATHODE)") (class "Default")
      (node (ref "D3") (pin "14") (pinfunction "7_CATHODE_14") (pintype "passive"))
      (node (ref "U8") (pin "16") (pinfunction "LED_NO.4_16") (pintype "passive"))
    )
    (net (code "52") (name "Net-(D3H-8_CATHODE)") (class "Default")
      (node (ref "D3") (pin "13") (pinfunction "8_CATHODE_13") (pintype "passive"))
      (node (ref "U8") (pin "17") (pinfunction "LED_NO.3_17") (pintype "passive"))
    )
    (net (code "53") (name "Net-(D3I-9_CATHODE)") (class "Default")
      (node (ref "D3") (pin "12") (pinfunction "9_CATHODE_12") (pintype "passive"))
      (node (ref "U8") (pin "18") (pinfunction "LED_NO.2_18") (pintype "passive"))
    )
    (net (code "54") (name "Net-(D3J-10_CATHODE)") (class "Default")
      (node (ref "D3") (pin "11") (pinfunction "10_CATHODE_11") (pintype "passive"))
      (node (ref "U8") (pin "1") (pinfunction "LED_NO.1_1") (pintype "passive"))
    )
    (net (code "55") (name "Net-(J1-Vin)") (class "Default")
      (node (ref "C1") (pin "1") (pinfunction "1_1") (pintype "passive"))
      (node (ref "J1") (pin "1") (pinfunction "Vin_1") (pintype "passive"))
      (node (ref "U9") (pin "1") (pinfunction "IN_1") (pintype "input"))
    )
    (net (code "56") (name "Net-(SD1-a)") (class "Default")
      (node (ref "R3") (pin "2") (pinfunction "2_2") (pintype "passive"))
      (node (ref "SD1") (pin "2") (pinfunction "a_2") (pintype "passive"))
    )
    (net (code "57") (name "Net-(SD1-b)") (class "Default")
      (node (ref "R1") (pin "2") (pinfunction "2_2") (pintype "passive"))
      (node (ref "SD1") (pin "1") (pinfunction "b_1") (pintype "passive"))
    )
    (net (code "58") (name "Net-(SD1-c)") (class "Default")
      (node (ref "R11") (pin "2") (pinfunction "2_2") (pintype "passive"))
      (node (ref "SD1") (pin "9") (pinfunction "c_9") (pintype "passive"))
    )
    (net (code "59") (name "Net-(SD1-d)") (class "Default")
      (node (ref "R13") (pin "2") (pinfunction "2_2") (pintype "passive"))
      (node (ref "SD1") (pin "7") (pinfunction "d_7") (pintype "passive"))
    )
    (net (code "60") (name "Net-(SD1-e)") (class "Default")
      (node (ref "R9") (pin "2") (pinfunction "2_2") (pintype "passive"))
      (node (ref "SD1") (pin "6") (pinfunction "e_6") (pintype "passive"))
    )
    (net (code "61") (name "Net-(SD1-f)") (class "Default")
      (node (ref "R5") (pin "2") (pinfunction "2_2") (pintype "passive"))
      (node (ref "SD1") (pin "4") (pinfunction "f_4") (pintype "passive"))
    )
    (net (code "62") (name "Net-(SD1-g)") (class "Default")
      (node (ref "R7") (pin "2") (pinfunction "2_2") (pintype "passive"))
      (node (ref "SD1") (pin "5") (pinfunction "g_5") (pintype "passive"))
    )
    (net (code "63") (name "Net-(SD2-a)") (class "Default")
      (node (ref "R6") (pin "1") (pinfunction "1_1") (pintype "passive"))
      (node (ref "SD2") (pin "2") (pinfunction "a_2") (pintype "passive"))
    )
    (net (code "64") (name "Net-(SD2-b)") (class "Default")
      (node (ref "R8") (pin "1") (pinfunction "1_1") (pintype "passive"))
      (node (ref "SD2") (pin "1") (pinfunction "b_1") (pintype "passive"))
    )
    (net (code "65") (name "Net-(SD2-c)") (class "Default")
      (node (ref "R10") (pin "1") (pinfunction "1_1") (pintype "passive"))
      (node (ref "SD2") (pin "9") (pinfunction "c_9") (pintype "passive"))
    )
    (net (code "66") (name "Net-(SD2-d)") (class "Default")
      (node (ref "R14") (pin "1") (pinfunction "1_1") (pintype "passive"))
      (node (ref "SD2") (pin "7") (pinfunction "d_7") (pintype "passive"))
    )
    (net (code "67") (name "Net-(SD2-e)") (class "Default")
      (node (ref "R12") (pin "1") (pinfunction "1_1") (pintype "passive"))
      (node (ref "SD2") (pin "6") (pinfunction "e_6") (pintype "passive"))
    )
    (net (code "68") (name "Net-(SD2-f)") (class "Default")
      (node (ref "R4") (pin "1") (pinfunction "1_1") (pintype "passive"))
      (node (ref "SD2") (pin "4") (pinfunction "f_4") (pintype "passive"))
    )
    (net (code "69") (name "Net-(SD2-g)") (class "Default")
      (node (ref "R2") (pin "1") (pinfunction "1_1") (pintype "passive"))
      (node (ref "SD2") (pin "5") (pinfunction "g_5") (pintype "passive"))
    )
    (net (code "70") (name "Net-(U1-A)") (class "Default")
      (node (ref "RP4") (pin "6") (pinfunction "6_6") (pintype "passive"))
      (node (ref "U1") (pin "7") (pinfunction "A_7") (pintype "input"))
      (node (ref "U6") (pin "4") (pinfunction "QE_4") (pintype "tri_state"))
    )
    (net (code "71") (name "Net-(U1-B)") (class "Default")
      (node (ref "RP4") (pin "7") (pinfunction "7_7") (pintype "passive"))
      (node (ref "U1") (pin "1") (pinfunction "B_1") (pintype "input"))
      (node (ref "U6") (pin "5") (pinfunction "QF_5") (pintype "tri_state"))
    )
    (net (code "72") (name "Net-(U1-C)") (class "Default")
      (node (ref "RP4") (pin "8") (pinfunction "8_8") (pintype "passive"))
      (node (ref "U1") (pin "2") (pinfunction "C_2") (pintype "input"))
      (node (ref "U6") (pin "6") (pinfunction "QG_6") (pintype "tri_state"))
    )
    (net (code "73") (name "Net-(U1-D)") (class "Default")
      (node (ref "RP4") (pin "9") (pinfunction "9_9") (pintype "passive"))
      (node (ref "U1") (pin "6") (pinfunction "D_6") (pintype "input"))
      (node (ref "U6") (pin "7") (pinfunction "QH_7") (pintype "tri_state"))
    )
    (net (code "74") (name "Net-(U1-~{a})") (class "Default")
      (node (ref "R3") (pin "1") (pinfunction "1_1") (pintype "passive"))
      (node (ref "U1") (pin "13") (pinfunction "~{a}_13") (pintype "open_collector"))
    )
    (net (code "75") (name "Net-(U1-~{b})") (class "Default")
      (node (ref "R1") (pin "1") (pinfunction "1_1") (pintype "passive"))
      (node (ref "U1") (pin "12") (pinfunction "~{b}_12") (pintype "open_collector"))
    )
    (net (code "76") (name "Net-(U1-~{c})") (class "Default")
      (node (ref "R11") (pin "1") (pinfunction "1_1") (pintype "passive"))
      (node (ref "U1") (pin "11") (pinfunction "~{c}_11") (pintype "open_collector"))
    )
    (net (code "77") (name "Net-(U1-~{d})") (class "Default")
      (node (ref "R13") (pin "1") (pinfunction "1_1") (pintype "passive"))
      (node (ref "U1") (pin "10") (pinfunction "~{d}_10") (pintype "open_collector"))
    )
    (net (code "78") (name "Net-(U1-~{e})") (class "Default")
      (node (ref "R9") (pin "1") (pinfunction "1_1") (pintype "passive"))
      (node (ref "U1") (pin "9") (pinfunction "~{e}_9") (pintype "open_collector"))
    )
    (net (code "79") (name "Net-(U1-~{f})") (class "Default")
      (node (ref "R5") (pin "1") (pinfunction "1_1") (pintype "passive"))
      (node (ref "U1") (pin "15") (pinfunction "~{f}_15") (pintype "open_collector"))
    )
    (net (code "80") (name "Net-(U1-~{g})") (class "Default")
      (node (ref "R7") (pin "1") (pinfunction "1_1") (pintype "passive"))
      (node (ref "U1") (pin "14") (pinfunction "~{g}_14") (pintype "open_collector"))
    )
    (net (code "81") (name "Net-(U2-A)") (class "Default")
      (node (ref "RP4") (pin "2") (pinfunction "2_2") (pintype "passive"))
      (node (ref "U2") (pin "7") (pinfunction "A_7") (pintype "input"))
      (node (ref "U6") (pin "15") (pinfunction "QA_15") (pintype "tri_state"))
    )
    (net (code "82") (name "Net-(U2-B)") (class "Default")
      (node (ref "RP4") (pin "3") (pinfunction "3_3") (pintype "passive"))
      (node (ref "U2") (pin "1") (pinfunction "B_1") (pintype "input"))
      (node (ref "U6") (pin "1") (pinfunction "QB_1") (pintype "tri_state"))
    )
    (net (code "83") (name "Net-(U2-C)") (class "Default")
      (node (ref "RP4") (pin "4") (pinfunction "4_4") (pintype "passive"))
      (node (ref "U2") (pin "2") (pinfunction "C_2") (pintype "input"))
      (node (ref "U6") (pin "2") (pinfunction "QC_2") (pintype "tri_state"))
    )
    (net (code "84") (name "Net-(U2-D)") (class "Default")
      (node (ref "RP4") (pin "5") (pinfunction "5_5") (pintype "passive"))
      (node (ref "U2") (pin "6") (pinfunction "D_6") (pintype "input"))
      (node (ref "U6") (pin "3") (pinfunction "QD_3") (pintype "tri_state"))
    )
    (net (code "85") (name "Net-(U2-~{a})") (class "Default")
      (node (ref "R6") (pin "2") (pinfunction "2_2") (pintype "passive"))
      (node (ref "U2") (pin "13") (pinfunction "~{a}_13") (pintype "open_collector"))
    )
    (net (code "86") (name "Net-(U2-~{b})") (class "Default")
      (node (ref "R8") (pin "2") (pinfunction "2_2") (pintype "passive"))
      (node (ref "U2") (pin "12") (pinfunction "~{b}_12") (pintype "open_collector"))
    )
    (net (code "87") (name "Net-(U2-~{c})") (class "Default")
      (node (ref "R10") (pin "2") (pinfunction "2_2") (pintype "passive"))
      (node (ref "U2") (pin "11") (pinfunction "~{c}_11") (pintype "open_collector"))
    )
    (net (code "88") (name "Net-(U2-~{d})") (class "Default")
      (node (ref "R14") (pin "2") (pinfunction "2_2") (pintype "passive"))
      (node (ref "U2") (pin "10") (pinfunction "~{d}_10") (pintype "open_collector"))
    )
    (net (code "89") (name "Net-(U2-~{e})") (class "Default")
      (node (ref "R12") (pin "2") (pinfunction "2_2") (pintype "passive"))
      (node (ref "U2") (pin "9") (pinfunction "~{e}_9") (pintype "open_collector"))
    )
    (net (code "90") (name "Net-(U2-~{f})") (class "Default")
      (node (ref "R4") (pin "2") (pinfunction "2_2") (pintype "passive"))
      (node (ref "U2") (pin "15") (pinfunction "~{f}_15") (pintype "open_collector"))
    )
    (net (code "91") (name "Net-(U2-~{g})") (class "Default")
      (node (ref "R2") (pin "2") (pinfunction "2_2") (pintype "passive"))
      (node (ref "U2") (pin "14") (pinfunction "~{g}_14") (pintype "open_collector"))
    )
    (net (code "92") (name "Net-(U7-PB6_(PCINT6{slash}XTAL1{slash}TOSC1))") (class "Default")
      (node (ref "C4") (pin "2") (pinfunction "2_2") (pintype "passive"))
      (node (ref "U7") (pin "9") (pinfunction "PB6_(PCINT6/XTAL1/TOSC1)_9") (pintype "bidirectional"))
      (node (ref "X1") (pin "1") (pinfunction "1_1") (pintype "passive"))
    )
    (net (code "93") (name "Net-(U7-PB7_(PCINT7{slash}XTAL2{slash}TOSC2))") (class "Default")
      (node (ref "C3") (pin "2") (pinfunction "2_2") (pintype "passive"))
      (node (ref "U7") (pin "10") (pinfunction "PB7_(PCINT7/XTAL2/TOSC2)_10") (pintype "bidirectional"))
      (node (ref "X1") (pin "2") (pinfunction "2_2") (pintype "passive"))
    )
    (net (code "94") (name "Net-(U8-DIVIDER(HIGH_END))") (class "Default")
      (node (ref "R18") (pin "2") (pinfunction "2_2") (pintype "passive"))
      (node (ref "U8") (pin "6") (pinfunction "DIVIDER(HIGH_END)_6") (pintype "passive"))
      (node (ref "U8") (pin "7") (pinfunction "REFERENCE_OUTPUT_7") (pintype "passive"))
    )
    (net (code "95") (name "Net-(U8-REFERENCE_ADJUST)") (class "Default")
      (node (ref "R17") (pin "1") (pinfunction "1_1") (pintype "passive"))
      (node (ref "R18") (pin "1") (pinfunction "1_1") (pintype "passive"))
      (node (ref "U8") (pin "8") (pinfunction "REFERENCE_ADJUST_8") (pintype "passive"))
    )
    (net (code "96") (name "Net-(U8-SIGNAL_INPUT)") (class "Default")
      (node (ref "C5") (pin "2") (pinfunction "2_2") (pintype "passive"))
      (node (ref "R19") (pin "2") (pinfunction "2_2") (pintype "passive"))
      (node (ref "U8") (pin "5") (pinfunction "SIGNAL_INPUT_5") (pintype "passive"))
    )
    (net (code "97") (name "VCC") (class "Default")
      (node (ref "BLK1") (pin "5") (pinfunction "VCC_5") (pintype "passive"))
      (node (ref "BLK2") (pin "5") (pinfunction "VCC_5") (pintype "passive"))
      (node (ref "BLK3") (pin "5") (pinfunction "VCC_5") (pintype "passive"))
      (node (ref "C2") (pin "1") (pinfunction "1_1") (pintype "passive"))
      (node (ref "D3") (pin "1") (pinfunction "1_ANODE_1") (pintype "passive"))
      (node (ref "D3") (pin "10") (pinfunction "10_ANODE_10") (pintype "passive"))
      (node (ref "D3") (pin "2") (pinfunction "2_ANODE_2") (pintype "passive"))
      (node (ref "D3") (pin "3") (pinfunction "3_ANODE_3") (pintype "passive"))
      (node (ref "D3") (pin "4") (pinfunction "4_ANODE_4") (pintype "passive"))
      (node (ref "D3") (pin "5") (pinfunction "5_ANODE_5") (pintype "passive"))
      (node (ref "D3") (pin "6") (pinfunction "6_ANODE_6") (pintype "passive"))
      (node (ref "D3") (pin "7") (pinfunction "7_ANODE_7") (pintype "passive"))
      (node (ref "D3") (pin "8") (pinfunction "8_ANODE_8") (pintype "passive"))
      (node (ref "D3") (pin "9") (pinfunction "9_ANODE_9") (pintype "passive"))
      (node (ref "SD1") (pin "3") (pinfunction "vcc_3") (pintype "passive"))
      (node (ref "SD1") (pin "8") (pinfunction "vcc_8") (pintype "passive"))
      (node (ref "SD2") (pin "3") (pinfunction "vcc_3") (pintype "passive"))
      (node (ref "SD2") (pin "8") (pinfunction "vcc_8") (pintype "passive"))
      (node (ref "U1") (pin "16") (pinfunction "VCC_16") (pintype "power_in"))
      (node (ref "U1") (pin "3") (pinfunction "~{LT}_3") (pintype "input"))
      (node (ref "U1") (pin "5") (pinfunction "~{RBI}_5") (pintype "input"))
      (node (ref "U2") (pin "16") (pinfunction "VCC_16") (pintype "power_in"))
      (node (ref "U2") (pin "3") (pinfunction "~{LT}_3") (pintype "input"))
      (node (ref "U2") (pin "5") (pinfunction "~{RBI}_5") (pintype "input"))
      (node (ref "U3") (pin "16") (pinfunction "VCC_16") (pintype "power_in"))
      (node (ref "U4") (pin "16") (pinfunction "VCC_16") (pintype "power_in"))
      (node (ref "U5") (pin "16") (pinfunction "VCC_16") (pintype "power_in"))
      (node (ref "U6") (pin "10") (pinfunction "~{SRCLR}_10") (pintype "input"))
      (node (ref "U6") (pin "16") (pinfunction "VCC_16") (pintype "power_in"))
      (node (ref "U7") (pin "20") (pinfunction "AVCC_20") (pintype "power_in"))
      (node (ref "U7") (pin "21") (pinfunction "AREF_21") (pintype "power_in"))
      (node (ref "U7") (pin "7") (pinfunction "VCC_7") (pintype "power_in"))
      (node (ref "U8") (pin "3") (pinfunction "V+_3") (pintype "power_in"))
      (node (ref "U8") (pin "9") (pinfunction "MODE_SELECT_9") (pintype "input"))
      (node (ref "U9") (pin "3") (pinfunction "OUT_3") (pintype "passive"))
    )
    (net (code "98") (name "unconnected-(PTH1-Pad1)") (class "Default")
      (node (ref "PTH1") (pin "1") (pinfunction "1_1") (pintype "passive"))
    )
    (net (code "99") (name "unconnected-(PTH2-Pad1)") (class "Default")
      (node (ref "PTH2") (pin "1") (pinfunction "1_1") (pintype "passive"))
    )
    (net (code "100") (name "unconnected-(PTH3-Pad1)") (class "Default")
      (node (ref "PTH3") (pin "1") (pinfunction "1_1") (pintype "passive"))
    )
    (net (code "101") (name "unconnected-(PTH4-Pad1)") (class "Default")
      (node (ref "PTH4") (pin "1") (pinfunction "1_1") (pintype "passive"))
    )
    (net (code "102") (name "unconnected-(RP1-Pad1)") (class "Default")
      (node (ref "RP1") (pin "1") (pinfunction "1_1") (pintype "passive"))
    )
    (net (code "103") (name "unconnected-(RP1-Pad2)") (class "Default")
      (node (ref "RP1") (pin "2") (pinfunction "2_2") (pintype "passive"))
    )
    (net (code "104") (name "unconnected-(RP1-Pad3)") (class "Default")
      (node (ref "RP1") (pin "3") (pinfunction "3_3") (pintype "passive"))
    )
    (net (code "105") (name "unconnected-(RP1-Pad4)") (class "Default")
      (node (ref "RP1") (pin "4") (pinfunction "4_4") (pintype "passive"))
    )
    (net (code "106") (name "unconnected-(RP1-Pad5)") (class "Default")
      (node (ref "RP1") (pin "5") (pinfunction "5_5") (pintype "passive"))
    )
    (net (code "107") (name "unconnected-(RP1-Pad6)") (class "Default")
      (node (ref "RP1") (pin "6") (pinfunction "6_6") (pintype "passive"))
    )
    (net (code "108") (name "unconnected-(RP1-Pad7)") (class "Default")
      (node (ref "RP1") (pin "7") (pinfunction "7_7") (pintype "passive"))
    )
    (net (code "109") (name "unconnected-(RP1-Pad8)") (class "Default")
      (node (ref "RP1") (pin "8") (pinfunction "8_8") (pintype "passive"))
    )
    (net (code "110") (name "unconnected-(RP1-Pad9)") (class "Default")
      (node (ref "RP1") (pin "9") (pinfunction "9_9") (pintype "passive"))
    )
    (net (code "111") (name "unconnected-(RP2-Pad1)") (class "Default")
      (node (ref "RP2") (pin "1") (pinfunction "1_1") (pintype "passive"))
    )
    (net (code "112") (name "unconnected-(RP2-Pad2)") (class "Default")
      (node (ref "RP2") (pin "2") (pinfunction "2_2") (pintype "passive"))
    )
    (net (code "113") (name "unconnected-(RP2-Pad3)") (class "Default")
      (node (ref "RP2") (pin "3") (pinfunction "3_3") (pintype "passive"))
    )
    (net (code "114") (name "unconnected-(RP2-Pad4)") (class "Default")
      (node (ref "RP2") (pin "4") (pinfunction "4_4") (pintype "passive"))
    )
    (net (code "115") (name "unconnected-(RP2-Pad5)") (class "Default")
      (node (ref "RP2") (pin "5") (pinfunction "5_5") (pintype "passive"))
    )
    (net (code "116") (name "unconnected-(RP2-Pad6)") (class "Default")
      (node (ref "RP2") (pin "6") (pinfunction "6_6") (pintype "passive"))
    )
    (net (code "117") (name "unconnected-(RP2-Pad7)") (class "Default")
      (node (ref "RP2") (pin "7") (pinfunction "7_7") (pintype "passive"))
    )
    (net (code "118") (name "unconnected-(RP2-Pad8)") (class "Default")
      (node (ref "RP2") (pin "8") (pinfunction "8_8") (pintype "passive"))
    )
    (net (code "119") (name "unconnected-(RP2-Pad9)") (class "Default")
      (node (ref "RP2") (pin "9") (pinfunction "9_9") (pintype "passive"))
    )
    (net (code "120") (name "unconnected-(RP3-Pad1)") (class "Default")
      (node (ref "RP3") (pin "1") (pinfunction "1_1") (pintype "passive"))
    )
    (net (code "121") (name "unconnected-(RP3-Pad2)") (class "Default")
      (node (ref "RP3") (pin "2") (pinfunction "2_2") (pintype "passive"))
    )
    (net (code "122") (name "unconnected-(RP3-Pad3)") (class "Default")
      (node (ref "RP3") (pin "3") (pinfunction "3_3") (pintype "passive"))
    )
    (net (code "123") (name "unconnected-(RP3-Pad4)") (class "Default")
      (node (ref "RP3") (pin "4") (pinfunction "4_4") (pintype "passive"))
    )
    (net (code "124") (name "unconnected-(RP3-Pad5)") (class "Default")
      (node (ref "RP3") (pin "5") (pinfunction "5_5") (pintype "passive"))
    )
    (net (code "125") (name "unconnected-(RP3-Pad6)") (class "Default")
      (node (ref "RP3") (pin "6") (pinfunction "6_6") (pintype "passive"))
    )
    (net (code "126") (name "unconnected-(RP3-Pad7)") (class "Default")
      (node (ref "RP3") (pin "7") (pinfunction "7_7") (pintype "passive"))
    )
    (net (code "127") (name "unconnected-(RP3-Pad8)") (class "Default")
      (node (ref "RP3") (pin "8") (pinfunction "8_8") (pintype "passive"))
    )
    (net (code "128") (name "unconnected-(RP3-Pad9)") (class "Default")
      (node (ref "RP3") (pin "9") (pinfunction "9_9") (pintype "passive"))
    )
    (net (code "129") (name "unconnected-(SD1-dp-Pad10)") (class "Default")
      (node (ref "SD1") (pin "10") (pinfunction "dp_10") (pintype "passive"))
    )
    (net (code "130") (name "unconnected-(SD2-dp-Pad10)") (class "Default")
      (node (ref "SD2") (pin "10") (pinfunction "dp_10") (pintype "passive"))
    )
    (net (code "131") (name "unconnected-(SW1-Pad2)") (class "Default")
      (node (ref "SW1") (pin "2") (pinfunction "2_2") (pintype "passive"))
    )
    (net (code "132") (name "unconnected-(SW1-Pad4)") (class "Default")
      (node (ref "SW1") (pin "4") (pinfunction "4_4") (pintype "passive"))
    )
    (net (code "133") (name "unconnected-(SW2-Pad2)") (class "Default")
      (node (ref "SW2") (pin "2") (pinfunction "2_2") (pintype "passive"))
    )
    (net (code "134") (name "unconnected-(SW2-Pad4)") (class "Default")
      (node (ref "SW2") (pin "4") (pinfunction "4_4") (pintype "passive"))
    )
    (net (code "135") (name "unconnected-(U3-QH-Pad9)") (class "Default")
      (node (ref "U3") (pin "9") (pinfunction "QH_9") (pintype "output"))
    )
    (net (code "136") (name "unconnected-(U4-QH-Pad9)") (class "Default")
      (node (ref "U4") (pin "9") (pinfunction "QH_9") (pintype "output"))
    )
    (net (code "137") (name "unconnected-(U5-QH-Pad9)") (class "Default")
      (node (ref "U5") (pin "9") (pinfunction "QH_9") (pintype "output"))
    )
    (net (code "138") (name "unconnected-(U6-QH'-Pad9)") (class "Default")
      (node (ref "U6") (pin "9") (pinfunction "QH'_9") (pintype "output"))
    )
    (net (code "139") (name "unconnected-(U7-PB5_(SCK{slash}PCINT5)-Pad19)") (class "Default")
      (node (ref "U7") (pin "19") (pinfunction "PB5_(SCK/PCINT5)_19") (pintype "bidirectional"))
    )
    (net (code "140") (name "unconnected-(U7-PC0_(ADC0{slash}PCINT8)-Pad23)") (class "Default")
      (node (ref "U7") (pin "23") (pinfunction "PC0_(ADC0/PCINT8)_23") (pintype "bidirectional"))
    )
    (net (code "141") (name "unconnected-(U7-PC4_(ADC4{slash}SDA{slash}PCINT12)-Pad27)") (class "Default")
      (node (ref "U7") (pin "27") (pinfunction "PC4_(ADC4/SDA/PCINT12)_27") (pintype "bidirectional"))
    )
    (net (code "142") (name "unconnected-(U7-PC5_(ADC5{slash}SCL{slash}PCINT13)-Pad28)") (class "Default")
      (node (ref "U7") (pin "28") (pinfunction "PC5_(ADC5/SCL/PCINT13)_28") (pintype "bidirectional"))
    )
    (net (code "143") (name "unconnected-(U7-PC6_(PCINT14{slash}~{RESET})-Pad1)") (class "Default")
      (node (ref "U7") (pin "1") (pinfunction "PC6_(PCINT14/~{RESET})_1") (pintype "bidirectional"))
    )
    (net (code "144") (name "unconnected-(U7-PD0_(PCINT16{slash}RXD)-Pad2)") (class "Default")
      (node (ref "U7") (pin "2") (pinfunction "PD0_(PCINT16/RXD)_2") (pintype "bidirectional"))
    )
    (net (code "145") (name "unconnected-(U7-PD1_(PCINT17{slash}TXD)-Pad3)") (class "Default")
      (node (ref "U7") (pin "3") (pinfunction "PD1_(PCINT17/TXD)_3") (pintype "bidirectional"))
    )
    (net (code "146") (name "unconnected-(U7-PD6_(PCINT22{slash}OC0A{slash}AIN0)-Pad12)") (class "Default")
      (node (ref "U7") (pin "12") (pinfunction "PD6_(PCINT22/OC0A/AIN0)_12") (pintype "bidirectional"))
    )
  )
)
